# MagicSwitchboard.net
KiCad netlist of a schematic drawn in EasyEDA
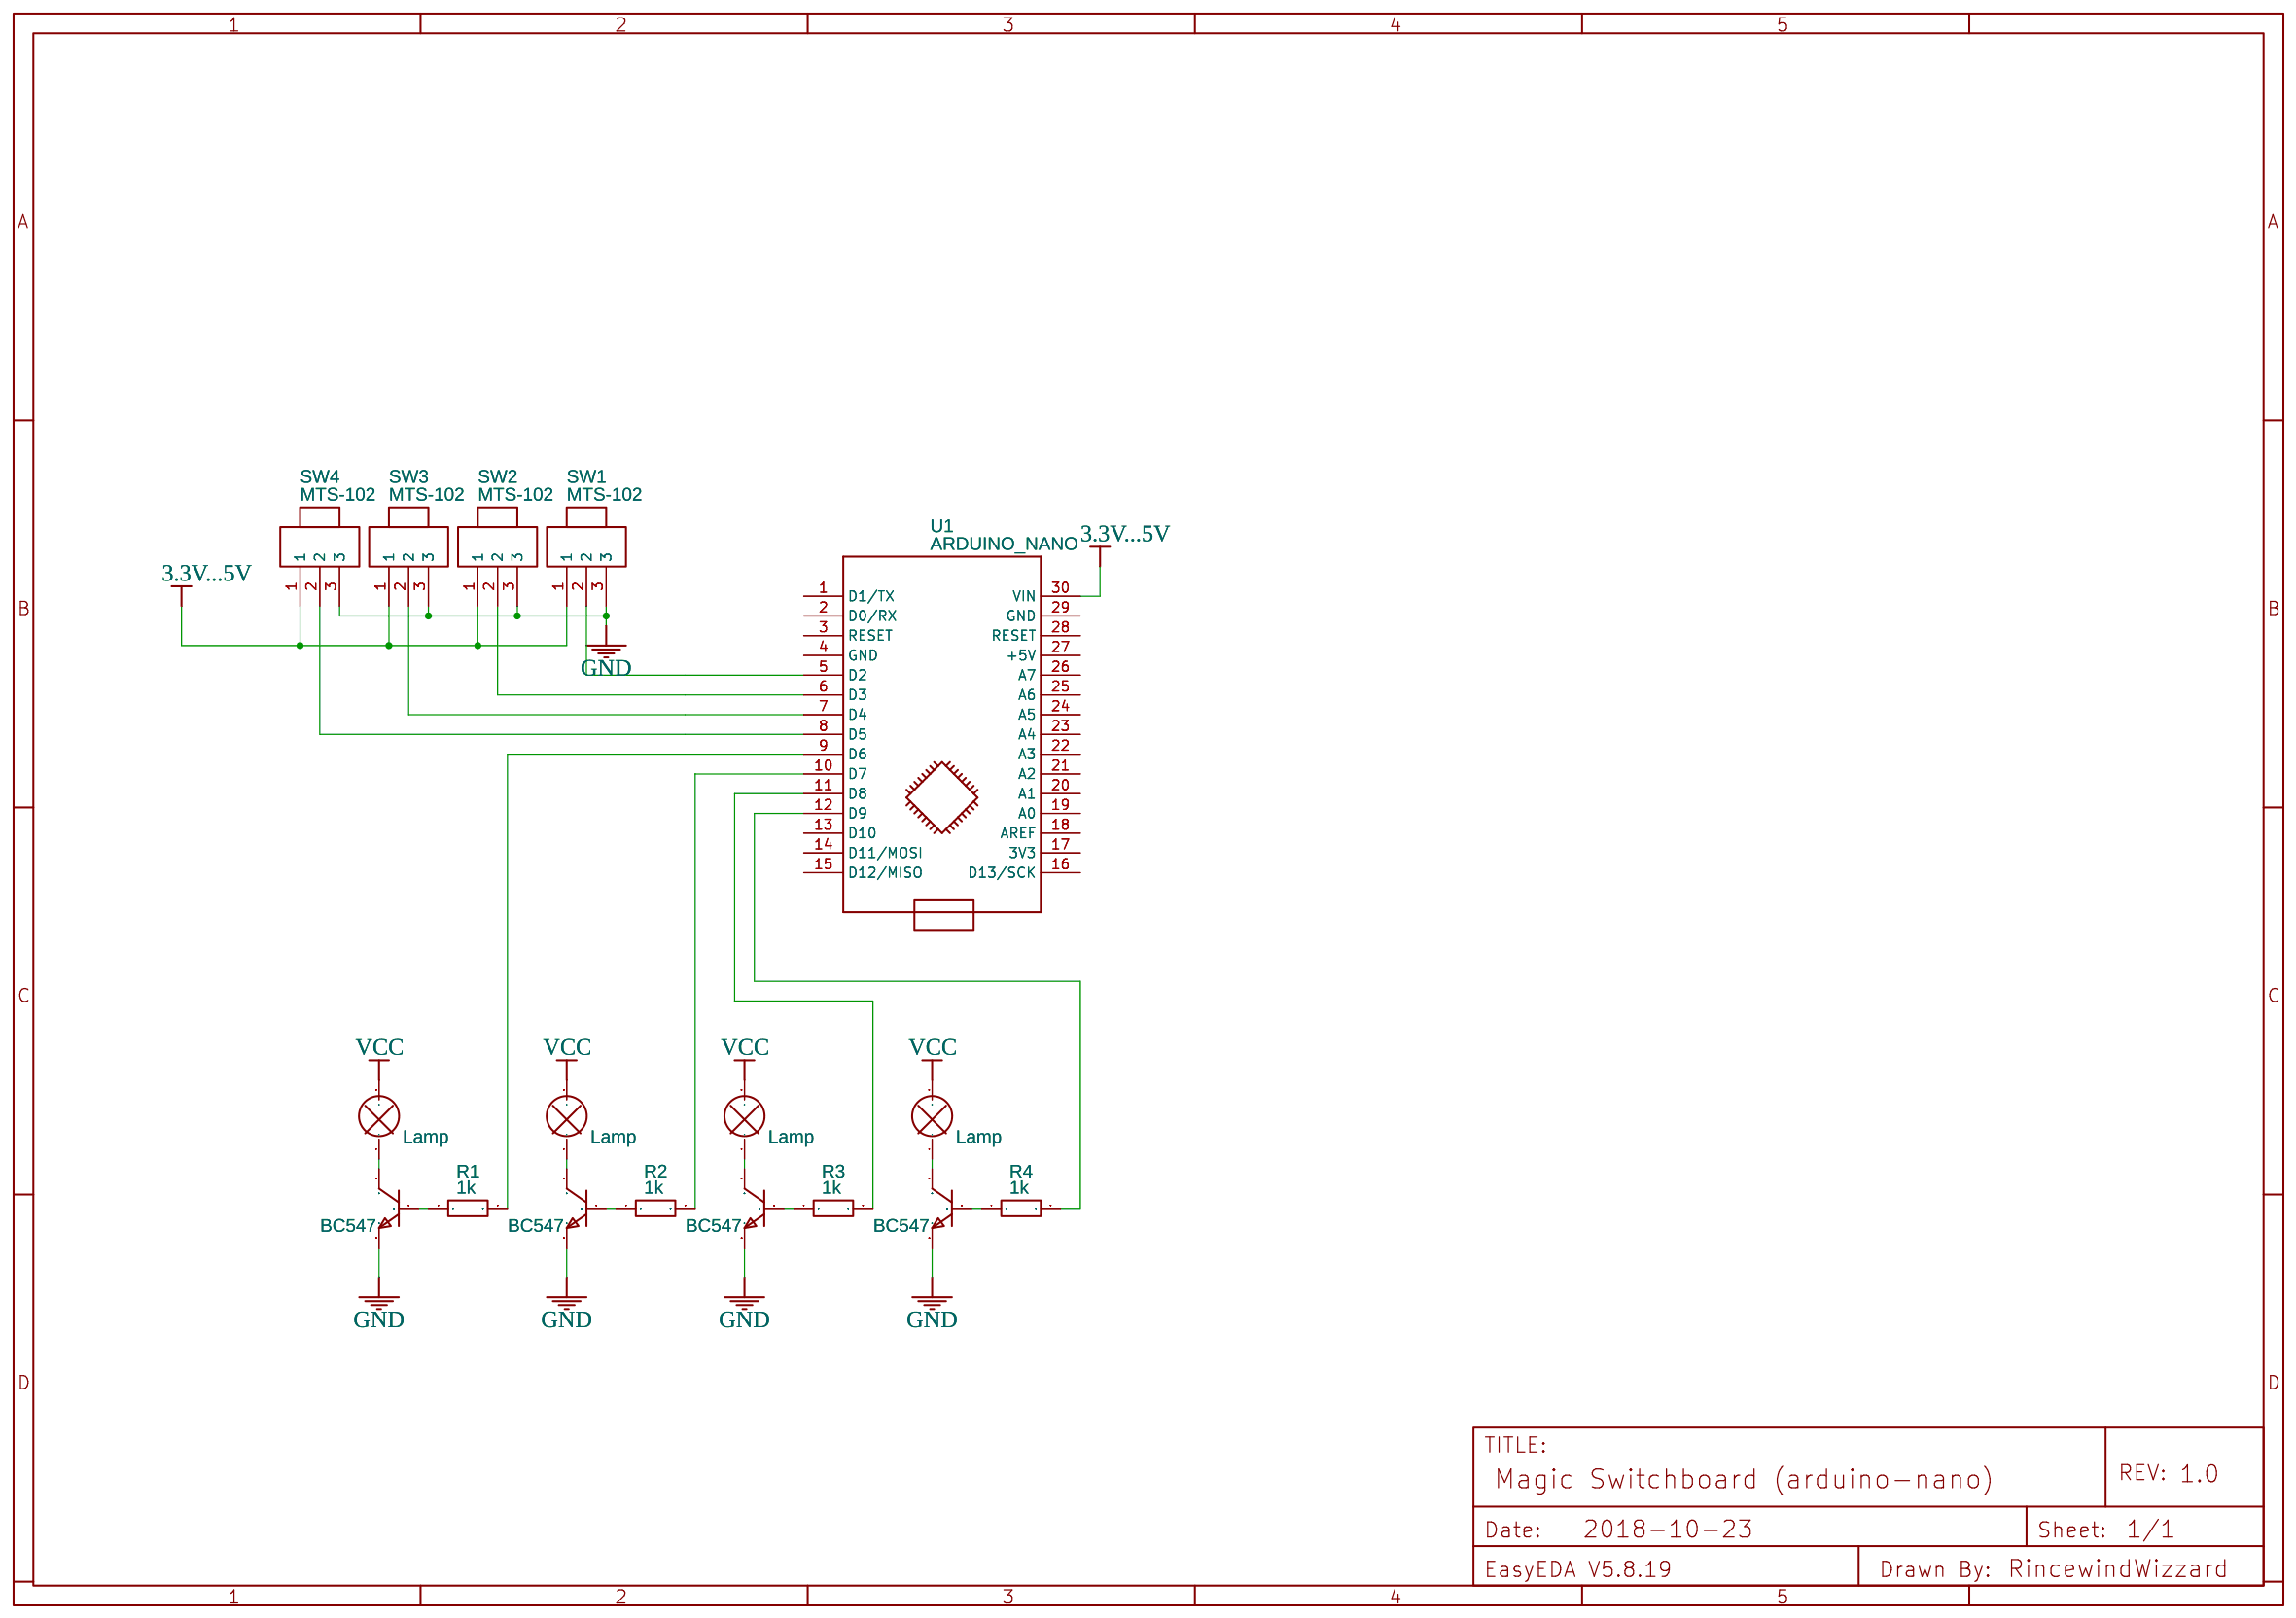
[diagram p0: schematic sheet]

(export (version "E")
  (design (tool "Eeschema 10.0.6"))
  (components
    (comp (ref "LA1")
      (value "Lamp")
      (fields (field (name "BOM_Manufacturer Part") "?"))
      (libsource (lib "") (part "Unknown_185_570"))
    )
    (comp (ref "LA2")
      (value "Lamp")
      (fields (field (name "BOM_Manufacturer Part") "?"))
      (libsource (lib "") (part "Unknown_280_570"))
    )
    (comp (ref "LA3")
      (value "Lamp")
      (fields (field (name "BOM_Manufacturer Part") "?"))
      (libsource (lib "") (part "Unknown_370_570"))
    )
    (comp (ref "LA4")
      (value "Lamp")
      (fields (field (name "BOM_Manufacturer Part") "?"))
      (libsource (lib "") (part "Unknown_465_570"))
    )
    (comp (ref "Q1")
      (value "BC547")
      (fields (field (name "BOM_Manufacturer Part") "BC547B Tube") (field (name "BOM_Supplier Part") "C2092"))
      (libsource (lib "") (part "Unknown_290_605"))
    )
    (comp (ref "Q2")
      (value "BC547")
      (fields (field (name "BOM_Manufacturer Part") "BC547B Tube") (field (name "BOM_Supplier Part") "C2092"))
      (libsource (lib "") (part "Unknown_380_605"))
    )
    (comp (ref "Q3")
      (value "BC547")
      (fields (field (name "BOM_Manufacturer Part") "BC547B Tube") (field (name "BOM_Supplier Part") "C2092"))
      (libsource (lib "") (part "Unknown_475_605"))
    )
    (comp (ref "Q5")
      (value "BC547")
      (fields (field (name "BOM_Manufacturer Part") "BC547B Tube") (field (name "BOM_Supplier Part") "C2092"))
      (libsource (lib "") (part "Unknown_195_605"))
    )
    (comp (ref "R1")
      (value "1k")
      (fields (field (name "BOM_Manufacturer Part") "?"))
      (libsource (lib "") (part "Res_AXIAL-0.3(1/8W)_EU"))
    )
    (comp (ref "R2")
      (value "1k")
      (fields (field (name "BOM_Manufacturer Part") "?"))
      (libsource (lib "") (part "Res_AXIAL-0.3(1/8W)_EU"))
    )
    (comp (ref "R3")
      (value "1k")
      (fields (field (name "BOM_Manufacturer Part") "?"))
      (libsource (lib "") (part "Res_AXIAL-0.3(1/8W)_EU"))
    )
    (comp (ref "R4")
      (value "1k")
      (fields (field (name "BOM_Manufacturer Part") "?"))
      (libsource (lib "") (part "Res_AXIAL-0.3(1/8W)_EU"))
    )
    (comp (ref "SW1")
      (value "MTS-102")
      (fields
        (field (name "BOM_Manufacturer Part") "Rocker switch601-10211BB")
        (field (name "BOM_Supplier Part") "C67849")
      )
      (libsource (lib "") (part "Unknown_290_270"))
    )
    (comp (ref "SW2")
      (value "MTS-102")
      (fields
        (field (name "BOM_Manufacturer Part") "Rocker switch601-10211BB")
        (field (name "BOM_Supplier Part") "C67849")
      )
      (libsource (lib "") (part "Unknown_245_270"))
    )
    (comp (ref "SW3")
      (value "MTS-102")
      (fields
        (field (name "BOM_Manufacturer Part") "Rocker switch601-10211BB")
        (field (name "BOM_Supplier Part") "C67849")
      )
      (libsource (lib "") (part "Unknown_200_270"))
    )
    (comp (ref "SW4")
      (value "MTS-102")
      (fields
        (field (name "BOM_Manufacturer Part") "Rocker switch601-10211BB")
        (field (name "BOM_Supplier Part") "C67849")
      )
      (libsource (lib "") (part "Unknown_155_270"))
    )
    (comp (ref "U1")
      (value "ARDUINO_NANO")
      (fields (field (name "BOM_Manufacturer Part") "?"))
      (libsource (lib "") (part "Unknown_470_365"))
    )
  )
  (nets
    (net (code "1") (name "3.3V...5V") (class "Default")
      (node (ref "SW1") (pin "1") (pinfunction "1_1") (pintype "unspecified"))
      (node (ref "SW2") (pin "1") (pinfunction "1_1") (pintype "unspecified"))
      (node (ref "SW3") (pin "1") (pinfunction "1_1") (pintype "unspecified"))
      (node (ref "SW4") (pin "1") (pinfunction "1_1") (pintype "unspecified"))
      (node (ref "U1") (pin "30") (pinfunction "VIN_30") (pintype "unspecified"))
    )
    (net (code "2") (name "GND") (class "Default")
      (node (ref "Q1") (pin "3") (pinfunction "E_3") (pintype "unspecified"))
      (node (ref "Q2") (pin "3") (pinfunction "E_3") (pintype "unspecified"))
      (node (ref "Q3") (pin "3") (pinfunction "E_3") (pintype "unspecified"))
      (node (ref "Q5") (pin "3") (pinfunction "E_3") (pintype "unspecified"))
      (node (ref "SW1") (pin "3") (pinfunction "3_3") (pintype "unspecified"))
      (node (ref "SW2") (pin "3") (pinfunction "3_3") (pintype "unspecified"))
      (node (ref "SW3") (pin "3") (pinfunction "3_3") (pintype "unspecified"))
      (node (ref "SW4") (pin "3") (pinfunction "3_3") (pintype "unspecified"))
    )
    (net (code "3") (name "Net-(LA1--)") (class "Default")
      (node (ref "LA1") (pin "1") (pinfunction "-_1") (pintype "unspecified"))
      (node (ref "Q5") (pin "1") (pinfunction "C_1") (pintype "unspecified"))
    )
    (net (code "4") (name "Net-(LA2--)") (class "Default")
      (node (ref "LA2") (pin "1") (pinfunction "-_1") (pintype "unspecified"))
      (node (ref "Q1") (pin "1") (pinfunction "C_1") (pintype "unspecified"))
    )
    (net (code "5") (name "Net-(LA3--)") (class "Default")
      (node (ref "LA3") (pin "1") (pinfunction "-_1") (pintype "unspecified"))
      (node (ref "Q2") (pin "1") (pinfunction "C_1") (pintype "unspecified"))
    )
    (net (code "6") (name "Net-(LA4--)") (class "Default")
      (node (ref "LA4") (pin "1") (pinfunction "-_1") (pintype "unspecified"))
      (node (ref "Q3") (pin "1") (pinfunction "C_1") (pintype "unspecified"))
    )
    (net (code "7") (name "Net-(Q1-B)") (class "Default")
      (node (ref "Q1") (pin "2") (pinfunction "B_2") (pintype "unspecified"))
      (node (ref "R2") (pin "1") (pinfunction "1_1") (pintype "unspecified"))
    )
    (net (code "8") (name "Net-(Q2-B)") (class "Default")
      (node (ref "Q2") (pin "2") (pinfunction "B_2") (pintype "unspecified"))
      (node (ref "R3") (pin "1") (pinfunction "1_1") (pintype "unspecified"))
    )
    (net (code "9") (name "Net-(Q3-B)") (class "Default")
      (node (ref "Q3") (pin "2") (pinfunction "B_2") (pintype "unspecified"))
      (node (ref "R4") (pin "1") (pinfunction "1_1") (pintype "unspecified"))
    )
    (net (code "10") (name "Net-(Q5-B)") (class "Default")
      (node (ref "Q5") (pin "2") (pinfunction "B_2") (pintype "unspecified"))
      (node (ref "R1") (pin "1") (pinfunction "1_1") (pintype "unspecified"))
    )
    (net (code "11") (name "Net-(U1-D2)") (class "Default")
      (node (ref "SW1") (pin "2") (pinfunction "2_2") (pintype "unspecified"))
      (node (ref "U1") (pin "5") (pinfunction "D2_5") (pintype "unspecified"))
    )
    (net (code "12") (name "Net-(U1-D3)") (class "Default")
      (node (ref "SW2") (pin "2") (pinfunction "2_2") (pintype "unspecified"))
      (node (ref "U1") (pin "6") (pinfunction "D3_6") (pintype "unspecified"))
    )
    (net (code "13") (name "Net-(U1-D4)") (class "Default")
      (node (ref "SW3") (pin "2") (pinfunction "2_2") (pintype "unspecified"))
      (node (ref "U1") (pin "7") (pinfunction "D4_7") (pintype "unspecified"))
    )
    (net (code "14") (name "Net-(U1-D5)") (class "Default")
      (node (ref "SW4") (pin "2") (pinfunction "2_2") (pintype "unspecified"))
      (node (ref "U1") (pin "8") (pinfunction "D5_8") (pintype "unspecified"))
    )
    (net (code "15") (name "Net-(U1-D6)") (class "Default")
      (node (ref "R1") (pin "2") (pinfunction "2_2") (pintype "unspecified"))
      (node (ref "U1") (pin "9") (pinfunction "D6_9") (pintype "unspecified"))
    )
    (net (code "16") (name "Net-(U1-D7)") (class "Default")
      (node (ref "R2") (pin "2") (pinfunction "2_2") (pintype "unspecified"))
      (node (ref "U1") (pin "10") (pinfunction "D7_10") (pintype "unspecified"))
    )
    (net (code "17") (name "Net-(U1-D8)") (class "Default")
      (node (ref "R3") (pin "2") (pinfunction "2_2") (pintype "unspecified"))
      (node (ref "U1") (pin "11") (pinfunction "D8_11") (pintype "unspecified"))
    )
    (net (code "18") (name "Net-(U1-D9)") (class "Default")
      (node (ref "R4") (pin "2") (pinfunction "2_2") (pintype "unspecified"))
      (node (ref "U1") (pin "12") (pinfunction "D9_12") (pintype "unspecified"))
    )
    (net (code "19") (name "VCC") (class "Default")
      (node (ref "LA1") (pin "2") (pinfunction "+_2") (pintype "unspecified"))
      (node (ref "LA2") (pin "2") (pinfunction "+_2") (pintype "unspecified"))
      (node (ref "LA3") (pin "2") (pinfunction "+_2") (pintype "unspecified"))
      (node (ref "LA4") (pin "2") (pinfunction "+_2") (pintype "unspecified"))
    )
    (net (code "20") (name "unconnected-(U1-+5V-Pad27)") (class "Default")
      (node (ref "U1") (pin "27") (pinfunction "+5V_27") (pintype "unspecified"))
    )
    (net (code "21") (name "unconnected-(U1-3V3-Pad17)") (class "Default")
      (node (ref "U1") (pin "17") (pinfunction "3V3_17") (pintype "unspecified"))
    )
    (net (code "22") (name "unconnected-(U1-A0-Pad19)") (class "Default")
      (node (ref "U1") (pin "19") (pinfunction "A0_19") (pintype "unspecified"))
    )
    (net (code "23") (name "unconnected-(U1-A1-Pad20)") (class "Default")
      (node (ref "U1") (pin "20") (pinfunction "A1_20") (pintype "unspecified"))
    )
    (net (code "24") (name "unconnected-(U1-A2-Pad21)") (class "Default")
      (node (ref "U1") (pin "21") (pinfunction "A2_21") (pintype "unspecified"))
    )
    (net (code "25") (name "unconnected-(U1-A3-Pad22)") (class "Default")
      (node (ref "U1") (pin "22") (pinfunction "A3_22") (pintype "unspecified"))
    )
    (net (code "26") (name "unconnected-(U1-A4-Pad23)") (class "Default")
      (node (ref "U1") (pin "23") (pinfunction "A4_23") (pintype "unspecified"))
    )
    (net (code "27") (name "unconnected-(U1-A5-Pad24)") (class "Default")
      (node (ref "U1") (pin "24") (pinfunction "A5_24") (pintype "unspecified"))
    )
    (net (code "28") (name "unconnected-(U1-A6-Pad25)") (class "Default")
      (node (ref "U1") (pin "25") (pinfunction "A6_25") (pintype "unspecified"))
    )
    (net (code "29") (name "unconnected-(U1-A7-Pad26)") (class "Default")
      (node (ref "U1") (pin "26") (pinfunction "A7_26") (pintype "unspecified"))
    )
    (net (code "30") (name "unconnected-(U1-AREF-Pad18)") (class "Default")
      (node (ref "U1") (pin "18") (pinfunction "AREF_18") (pintype "unspecified"))
    )
    (net (code "31") (name "unconnected-(U1-D0{slash}RX-Pad2)") (class "Default")
      (node (ref "U1") (pin "2") (pinfunction "D0/RX_2") (pintype "unspecified"))
    )
    (net (code "32") (name "unconnected-(U1-D1{slash}TX-Pad1)") (class "Default")
      (node (ref "U1") (pin "1") (pinfunction "D1/TX_1") (pintype "unspecified"))
    )
    (net (code "33") (name "unconnected-(U1-D10-Pad13)") (class "Default")
      (node (ref "U1") (pin "13") (pinfunction "D10_13") (pintype "unspecified"))
    )
    (net (code "34") (name "unconnected-(U1-D11{slash}MOSI-Pad14)") (class "Default")
      (node (ref "U1") (pin "14") (pinfunction "D11/MOSI_14") (pintype "unspecified"))
    )
    (net (code "35") (name "unconnected-(U1-D12{slash}MISO-Pad15)") (class "Default")
      (node (ref "U1") (pin "15") (pinfunction "D12/MISO_15") (pintype "unspecified"))
    )
    (net (code "36") (name "unconnected-(U1-D13{slash}SCK-Pad16)") (class "Default")
      (node (ref "U1") (pin "16") (pinfunction "D13/SCK_16") (pintype "unspecified"))
    )
    (net (code "37") (name "unconnected-(U1-GND-Pad4)") (class "Default")
      (node (ref "U1") (pin "4") (pinfunction "GND_4") (pintype "unspecified"))
    )
    (net (code "38") (name "unconnected-(U1-GND-Pad29)") (class "Default")
      (node (ref "U1") (pin "29") (pinfunction "GND_29") (pintype "unspecified"))
    )
    (net (code "39") (name "unconnected-(U1-RESET-Pad3)") (class "Default")
      (node (ref "U1") (pin "3") (pinfunction "RESET_3") (pintype "unspecified"))
    )
    (net (code "40") (name "unconnected-(U1-RESET-Pad28)") (class "Default")
      (node (ref "U1") (pin "28") (pinfunction "RESET_28") (pintype "unspecified"))
    )
  )
)
